# data_interface.net
KiCad netlist of a schematic drawn in Altium Designer
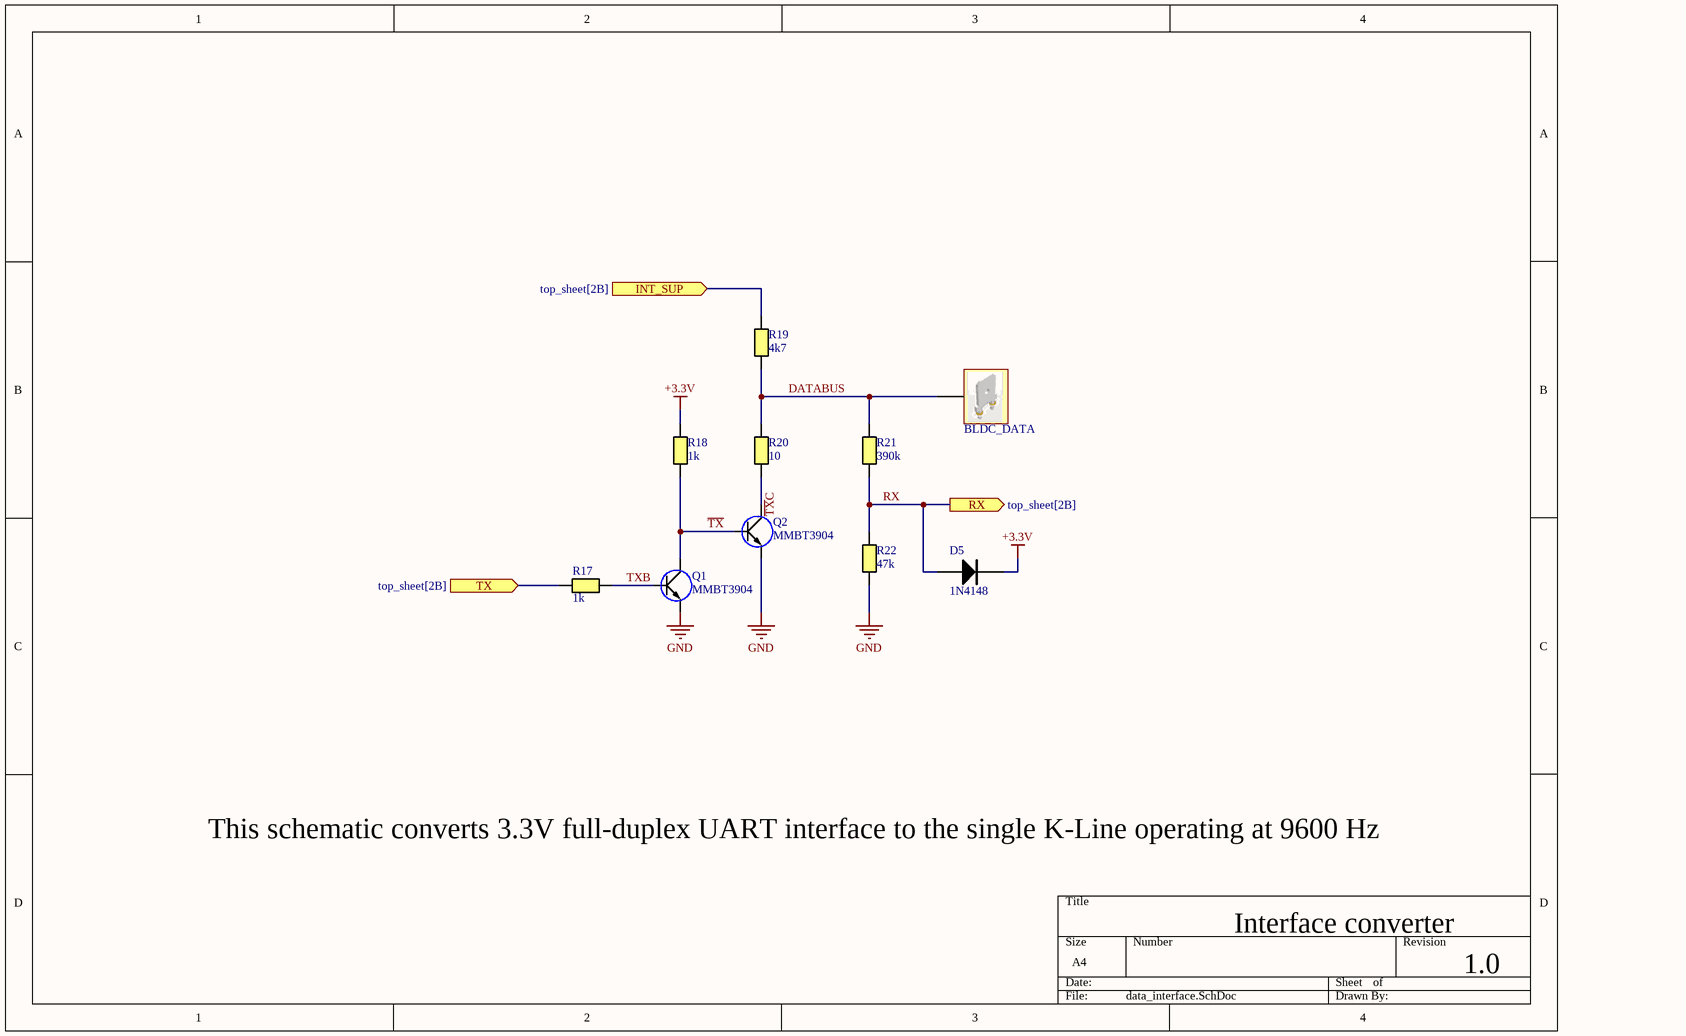
[diagram p0: data_interface.SchDoc]

(export (version "E")
  (design (tool "Eeschema 10.0.6"))
  (components
    (comp (ref "BLDC_DATA")
      (value "Crimp 6.3 single PCB")
      (footprint "Crimp 6.3mm single PCB")
      (description "Straight Mount Angle PCB Tab Terminal")
      (libsource (lib "Connectors") (part "Crimp 6.3 single PCB"))
    )
    (comp (ref "D5")
      (value "1N4148")
      (footprint "SOD80")
      (description "Small Signal Fast Switching Diodes")
      (libsource (lib "Diodes") (part "1N4148"))
    )
    (comp (ref "Q1")
      (value "MMBT3904")
      (footprint "SOT23")
      (description "NPN General Purpose Transistor")
      (libsource (lib "Transistors") (part "2N3904"))
    )
    (comp (ref "Q2")
      (value "MMBT3904")
      (footprint "SOT23")
      (description "NPN General Purpose Transistor")
      (libsource (lib "Transistors") (part "2N3904"))
    )
    (comp (ref "R17")
      (value "1k")
      (footprint "RESC0603(1608)_N")
      (description "Resistor Medium Density")
      (libsource (lib "") (part "Resistor M_1"))
    )
    (comp (ref "R18")
      (value "1k")
      (footprint "RESC0603(1608)_N")
      (description "Resistor Medium Density")
      (libsource (lib "Discrete") (part "Resistor M"))
    )
    (comp (ref "R19")
      (value "4k7")
      (footprint "RESC0603(1608)_N")
      (description "Resistor Medium Density")
      (libsource (lib "Discrete") (part "Resistor M"))
    )
    (comp (ref "R20")
      (value "10")
      (footprint "RESC0603(1608)_N")
      (description "Resistor Medium Density")
      (libsource (lib "Discrete") (part "Resistor M"))
    )
    (comp (ref "R21")
      (value "390k")
      (footprint "RESC0603(1608)_N")
      (description "Resistor Medium Density")
      (libsource (lib "Discrete") (part "Resistor M"))
    )
    (comp (ref "R22")
      (value "47k")
      (footprint "RESC0603(1608)_N")
      (description "Resistor Medium Density")
      (libsource (lib "Discrete") (part "Resistor M"))
    )
  )
  (nets
    (net (code "1") (name "+3.3V") (class "Default")
      (node (ref "D5") (pin "2") (pinfunction "K_2") (pintype "passive"))
      (node (ref "R18") (pin "2") (pinfunction "2_2") (pintype "passive"))
    )
    (net (code "2") (name "/DATABUS") (class "Default")
      (node (ref "BLDC_DATA") (pin "1") (pintype "passive"))
      (node (ref "R19") (pin "1") (pinfunction "1_1") (pintype "passive"))
      (node (ref "R20") (pin "2") (pinfunction "2_2") (pintype "passive"))
      (node (ref "R21") (pin "2") (pinfunction "2_2") (pintype "passive"))
    )
    (net (code "3") (name "/INT_SUP") (class "Default")
      (node (ref "R19") (pin "2") (pinfunction "2_2") (pintype "passive"))
    )
    (net (code "4") (name "/RX") (class "Default")
      (node (ref "D5") (pin "1") (pinfunction "A_1") (pintype "passive"))
      (node (ref "R21") (pin "1") (pinfunction "1_1") (pintype "passive"))
      (node (ref "R22") (pin "2") (pinfunction "2_2") (pintype "passive"))
    )
    (net (code "5") (name "/TX") (class "Default")
      (node (ref "R17") (pin "1") (pinfunction "1_1") (pintype "passive"))
    )
    (net (code "6") (name "/TXB") (class "Default")
      (node (ref "Q1") (pin "1") (pinfunction "B_1") (pintype "passive"))
      (node (ref "R17") (pin "2") (pinfunction "2_2") (pintype "passive"))
    )
    (net (code "7") (name "/~{TX}") (class "Default")
      (node (ref "Q1") (pin "3") (pinfunction "C_3") (pintype "passive"))
      (node (ref "Q2") (pin "1") (pinfunction "B_1") (pintype "passive"))
      (node (ref "R18") (pin "1") (pinfunction "1_1") (pintype "passive"))
    )
    (net (code "8") (name "/~{TX}C") (class "Default")
      (node (ref "Q2") (pin "3") (pinfunction "C_3") (pintype "passive"))
      (node (ref "R20") (pin "1") (pinfunction "1_1") (pintype "passive"))
    )
    (net (code "9") (name "GND") (class "Default")
      (node (ref "Q1") (pin "2") (pinfunction "E_2") (pintype "passive"))
      (node (ref "Q2") (pin "2") (pinfunction "E_2") (pintype "passive"))
      (node (ref "R22") (pin "1") (pinfunction "1_1") (pintype "passive"))
    )
  )
)
